# untitled.net
KiCad netlist of a schematic drawn in EAGLE
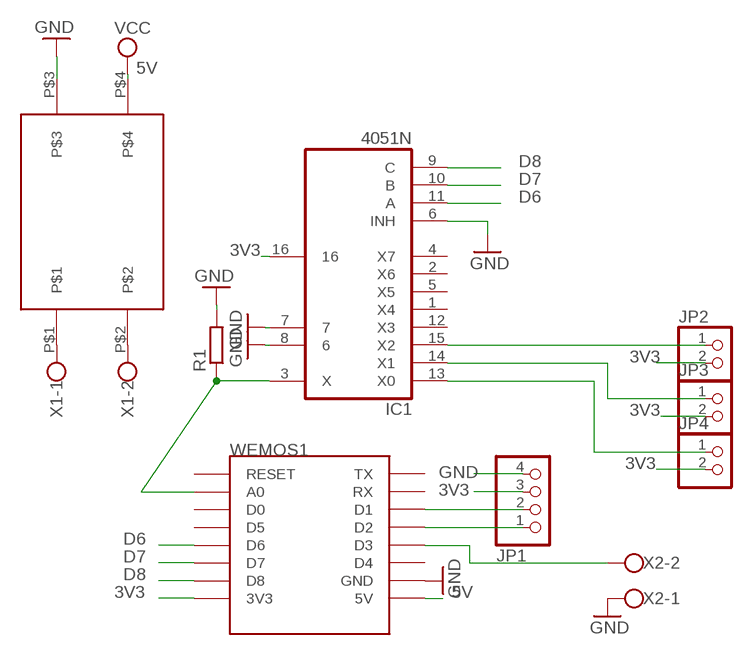
[diagram p0: schematic, sheet 1]

(export (version "E")
  (design (tool "Eeschema 10.0.6"))
  (components
    (comp (ref "IC1")
      (value "4051N")
      (footprint "eagle-import:DIL16")
      (libsource (lib "eagle-import") (part "4051N"))
    )
    (comp (ref "JP1")
      (value "PINHD-1X4")
      (footprint "eagle-import:1X04")
      (libsource (lib "eagle-import") (part "PINHD-1X4"))
    )
    (comp (ref "JP2")
      (value "PINHD-1X2")
      (footprint "eagle-import:1X02")
      (libsource (lib "eagle-import") (part "PINHD-1X2"))
    )
    (comp (ref "JP3")
      (value "PINHD-1X2")
      (footprint "eagle-import:1X02")
      (libsource (lib "eagle-import") (part "PINHD-1X2"))
    )
    (comp (ref "JP4")
      (value "PINHD-1X2")
      (footprint "eagle-import:1X02")
      (libsource (lib "eagle-import") (part "PINHD-1X2"))
    )
    (comp (ref "R1")
      (value "R-EU_0207/10")
      (footprint "eagle-import:0207_10")
      (libsource (lib "eagle-import") (part "R-EU_0207/10"))
    )
    (comp (ref "U$6")
      (value "HLK-PM01")
      (footprint "eagle-import:HLK-PM01")
      (libsource (lib "eagle-import") (part "HLK-PM01"))
    )
    (comp (ref "WEMOS1")
      (value "WEMOS-D1-MINI")
      (footprint "eagle-import:WEMOS-D1-MINI")
      (libsource (lib "eagle-import") (part "WEMOS-D1-MINI"))
    )
    (comp (ref "X1")
      (value "W237-102")
      (footprint "eagle-import:W237-102")
      (fields (field (name "MPN") "237-102"))
      (libsource (lib "eagle-import") (part "W237-102"))
    )
    (comp (ref "X2")
      (value "W237-102")
      (footprint "eagle-import:W237-102")
      (fields (field (name "MPN") "237-102"))
      (libsource (lib "eagle-import") (part "W237-102"))
    )
  )
  (nets
    (net (code "1") (name "/3V3") (class "Default")
      (node (ref "IC1") (pin "16") (pinfunction "16_16") (pintype "power_in"))
      (node (ref "JP1") (pin "3") (pinfunction "3_3") (pintype "passive"))
      (node (ref "JP2") (pin "2") (pinfunction "2_2") (pintype "passive"))
      (node (ref "JP3") (pin "2") (pinfunction "2_2") (pintype "passive"))
      (node (ref "JP4") (pin "2") (pinfunction "2_2") (pintype "passive"))
      (node (ref "WEMOS1") (pin "3V3") (pinfunction "3V3_3V3") (pintype "bidirectional"))
    )
    (net (code "2") (name "/D6") (class "Default")
      (node (ref "IC1") (pin "11") (pinfunction "A_11") (pintype "input"))
      (node (ref "WEMOS1") (pin "D6") (pinfunction "D6_D6") (pintype "bidirectional"))
    )
    (net (code "3") (name "/D7") (class "Default")
      (node (ref "IC1") (pin "10") (pinfunction "B_10") (pintype "input"))
      (node (ref "WEMOS1") (pin "D7") (pinfunction "D7_D7") (pintype "bidirectional"))
    )
    (net (code "4") (name "/D8") (class "Default")
      (node (ref "IC1") (pin "9") (pinfunction "C_9") (pintype "input"))
      (node (ref "WEMOS1") (pin "D8") (pinfunction "D8_D8") (pintype "bidirectional"))
    )
    (net (code "5") (name "GND") (class "Default")
      (node (ref "IC1") (pin "6") (pinfunction "INH_6") (pintype "input"))
      (node (ref "IC1") (pin "7") (pinfunction "7_7") (pintype "bidirectional"))
      (node (ref "IC1") (pin "8") (pinfunction "6_8") (pintype "bidirectional"))
      (node (ref "JP1") (pin "4") (pinfunction "4_4") (pintype "passive"))
      (node (ref "R1") (pin "2") (pinfunction "2_2") (pintype "passive"))
      (node (ref "U$6") (pin "P$3") (pinfunction "P$3_P$3") (pintype "bidirectional"))
      (node (ref "WEMOS1") (pin "GND") (pinfunction "GND_GND") (pintype "bidirectional"))
      (node (ref "X2") (pin "1") (pinfunction "KL_1") (pintype "passive"))
    )
    (net (code "6") (name "Net-(IC1-X)") (class "Default")
      (node (ref "IC1") (pin "3") (pinfunction "X_3") (pintype "bidirectional"))
      (node (ref "R1") (pin "1") (pinfunction "1_1") (pintype "passive"))
      (node (ref "WEMOS1") (pin "A0") (pinfunction "A0_A0") (pintype "bidirectional"))
    )
    (net (code "7") (name "Net-(IC1-X0)") (class "Default")
      (node (ref "IC1") (pin "13") (pinfunction "X0_13") (pintype "bidirectional"))
      (node (ref "JP4") (pin "1") (pinfunction "1_1") (pintype "passive"))
    )
    (net (code "8") (name "Net-(IC1-X1)") (class "Default")
      (node (ref "IC1") (pin "14") (pinfunction "X1_14") (pintype "bidirectional"))
      (node (ref "JP3") (pin "1") (pinfunction "1_1") (pintype "passive"))
    )
    (net (code "9") (name "Net-(IC1-X2)") (class "Default")
      (node (ref "IC1") (pin "15") (pinfunction "X2_15") (pintype "bidirectional"))
      (node (ref "JP2") (pin "1") (pinfunction "1_1") (pintype "passive"))
    )
    (net (code "10") (name "Net-(JP1-Pad1)") (class "Default")
      (node (ref "JP1") (pin "1") (pinfunction "1_1") (pintype "passive"))
      (node (ref "WEMOS1") (pin "D2") (pinfunction "D2_D2") (pintype "bidirectional"))
    )
    (net (code "11") (name "Net-(JP1-Pad2)") (class "Default")
      (node (ref "JP1") (pin "2") (pinfunction "2_2") (pintype "passive"))
      (node (ref "WEMOS1") (pin "D1") (pinfunction "D1_D1") (pintype "bidirectional"))
    )
    (net (code "12") (name "Net-(X1A-KL)") (class "Default")
      (node (ref "U$6") (pin "P$1") (pinfunction "P$1_P$1") (pintype "bidirectional"))
      (node (ref "X1") (pin "1") (pinfunction "KL_1") (pintype "passive"))
    )
    (net (code "13") (name "Net-(X1B-KL)") (class "Default")
      (node (ref "U$6") (pin "P$2") (pinfunction "P$2_P$2") (pintype "bidirectional"))
      (node (ref "X1") (pin "2") (pinfunction "KL_2") (pintype "passive"))
    )
    (net (code "14") (name "Net-(X2B-KL)") (class "Default")
      (node (ref "WEMOS1") (pin "D3") (pinfunction "D3_D3") (pintype "bidirectional"))
      (node (ref "X2") (pin "2") (pinfunction "KL_2") (pintype "passive"))
    )
    (net (code "15") (name "VCC") (class "Default")
      (node (ref "U$6") (pin "P$4") (pinfunction "P$4_P$4") (pintype "bidirectional"))
      (node (ref "WEMOS1") (pin "5V") (pinfunction "5V_5V") (pintype "bidirectional"))
    )
    (net (code "16") (name "unconnected-(IC1-X3-Pad12)") (class "Default")
      (node (ref "IC1") (pin "12") (pinfunction "X3_12") (pintype "bidirectional"))
    )
    (net (code "17") (name "unconnected-(IC1-X4-Pad1)") (class "Default")
      (node (ref "IC1") (pin "1") (pinfunction "X4_1") (pintype "bidirectional"))
    )
    (net (code "18") (name "unconnected-(IC1-X5-Pad5)") (class "Default")
      (node (ref "IC1") (pin "5") (pinfunction "X5_5") (pintype "bidirectional"))
    )
    (net (code "19") (name "unconnected-(IC1-X6-Pad2)") (class "Default")
      (node (ref "IC1") (pin "2") (pinfunction "X6_2") (pintype "bidirectional"))
    )
    (net (code "20") (name "unconnected-(IC1-X7-Pad4)") (class "Default")
      (node (ref "IC1") (pin "4") (pinfunction "X7_4") (pintype "bidirectional"))
    )
    (net (code "21") (name "unconnected-(WEMOS1-PadD0)") (class "Default")
      (node (ref "WEMOS1") (pin "D0") (pinfunction "D0_D0") (pintype "bidirectional"))
    )
    (net (code "22") (name "unconnected-(WEMOS1-PadD4)") (class "Default")
      (node (ref "WEMOS1") (pin "D4") (pinfunction "D4_D4") (pintype "bidirectional"))
    )
    (net (code "23") (name "unconnected-(WEMOS1-PadD5)") (class "Default")
      (node (ref "WEMOS1") (pin "D5") (pinfunction "D5_D5") (pintype "bidirectional"))
    )
    (net (code "24") (name "unconnected-(WEMOS1-PadRESET)") (class "Default")
      (node (ref "WEMOS1") (pin "RESET") (pinfunction "RESET_RESET") (pintype "bidirectional"))
    )
    (net (code "25") (name "unconnected-(WEMOS1-PadRX)") (class "Default")
      (node (ref "WEMOS1") (pin "RX") (pinfunction "RX_RX") (pintype "bidirectional"))
    )
    (net (code "26") (name "unconnected-(WEMOS1-PadTX)") (class "Default")
      (node (ref "WEMOS1") (pin "TX") (pinfunction "TX_TX") (pintype "bidirectional"))
    )
  )
)
